# LightingUPS_v2b.net
KiCad netlist of a schematic drawn in EAGLE
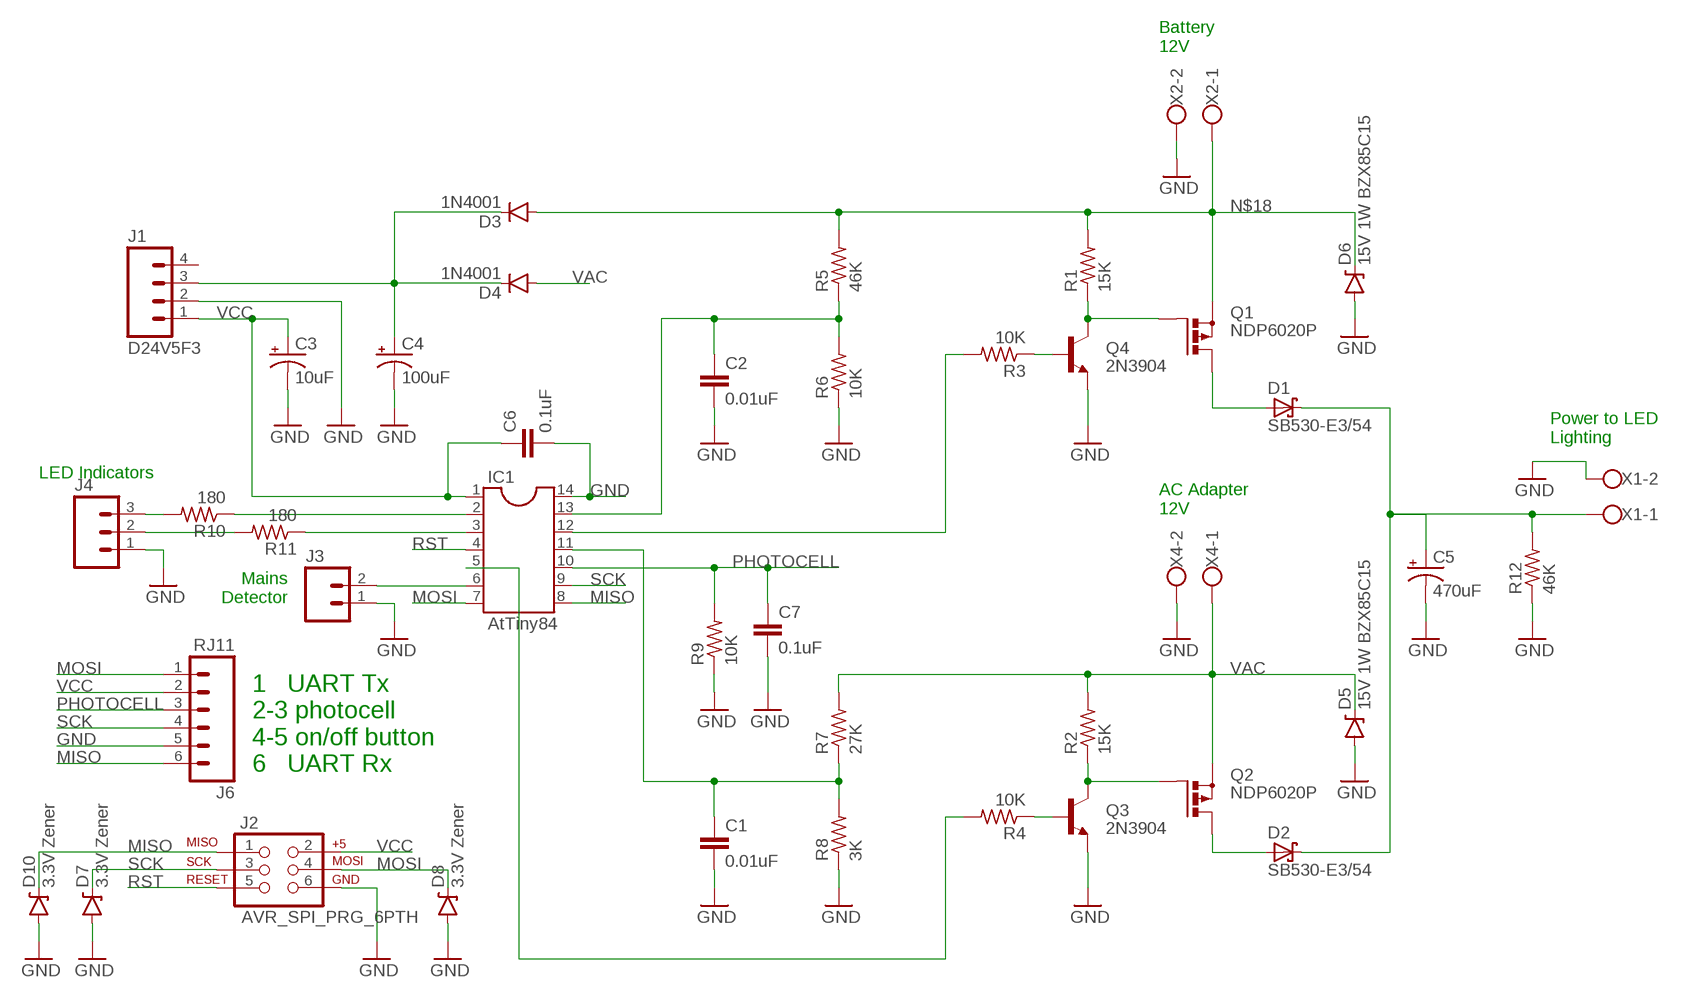
[diagram p0: schematic, sheet 1]

(export (version "E")
  (design (tool "Eeschema 10.0.6"))
  (components
    (comp (ref "C1")
      (value "0.01uF")
      (footprint "eagle-import:CAP-PTH-5MM")
      (libsource (lib "eagle-import") (part "SparkFun-Passives_CAPPTH1"))
    )
    (comp (ref "C2")
      (value "0.01uF")
      (footprint "eagle-import:CAP-PTH-5MM")
      (libsource (lib "eagle-import") (part "SparkFun-Passives_CAPPTH1"))
    )
    (comp (ref "C3")
      (value "10uF")
      (footprint "eagle-import:CPOL-RADIAL-100UF-25V")
      (libsource (lib "eagle-import") (part "CAP_POLPTH1"))
    )
    (comp (ref "C4")
      (value "100uF")
      (footprint "eagle-import:CPOL-RADIAL-100UF-25V")
      (libsource (lib "eagle-import") (part "CAP_POLPTH1"))
    )
    (comp (ref "C5")
      (value "470uF")
      (footprint "eagle-import:CPOL-RADIAL-1000UF-25V")
      (libsource (lib "eagle-import") (part "CAP_POLPTH4"))
    )
    (comp (ref "C6")
      (value "0.1uF")
      (footprint "eagle-import:CAP-PTH-SMALL")
      (libsource (lib "eagle-import") (part "CAPPTH"))
    )
    (comp (ref "C7")
      (value "0.1uF")
      (footprint "eagle-import:CAP-PTH-SMALL")
      (libsource (lib "eagle-import") (part "CAPPTH"))
    )
    (comp (ref "D1")
      (value "SB530-E3/54")
      (footprint "eagle-import:DO201T15")
      (libsource (lib "eagle-import") (part "SCHOTTKY-DIODEDO201T15"))
    )
    (comp (ref "D2")
      (value "SB530-E3/54")
      (footprint "eagle-import:DO201T15")
      (libsource (lib "eagle-import") (part "SCHOTTKY-DIODEDO201T15"))
    )
    (comp (ref "D3")
      (value "1N4001")
      (footprint "eagle-import:DIODE-1N4001")
      (libsource (lib "eagle-import") (part "DIODEPTH"))
    )
    (comp (ref "D4")
      (value "1N4001")
      (footprint "eagle-import:DIODE-1N4001")
      (libsource (lib "eagle-import") (part "DIODEPTH"))
    )
    (comp (ref "D5")
      (value "15V 1W BZX85C15")
      (footprint "eagle-import:DIODE-ZENER")
      (libsource (lib "eagle-import") (part "DIODE-ZENERPTH"))
    )
    (comp (ref "D6")
      (value "15V 1W BZX85C15")
      (footprint "eagle-import:DIODE-ZENER")
      (libsource (lib "eagle-import") (part "DIODE-ZENERPTH"))
    )
    (comp (ref "D7")
      (value "3.3V Zener")
      (footprint "eagle-import:DIODE-ZENER")
      (libsource (lib "eagle-import") (part "DIODE-ZENERPTH"))
    )
    (comp (ref "D8")
      (value "3.3V Zener")
      (footprint "eagle-import:DIODE-ZENER")
      (libsource (lib "eagle-import") (part "DIODE-ZENERPTH"))
    )
    (comp (ref "D10")
      (value "3.3V Zener")
      (footprint "eagle-import:DIODE-ZENER")
      (libsource (lib "eagle-import") (part "DIODE-ZENERPTH"))
    )
    (comp (ref "IC1")
      (value "AtTiny84")
      (footprint "eagle-import:DIL14")
      (libsource (lib "eagle-import") (part "DIL14"))
    )
    (comp (ref "J1")
      (value "D24V5F3")
      (footprint "eagle-import:1X04")
      (libsource (lib "eagle-import") (part "M04PTH"))
    )
    (comp (ref "J2")
      (value "AVR_SPI_PRG_6PTH")
      (footprint "eagle-import:2X3")
      (libsource (lib "eagle-import") (part "AVR_SPI_PRG_6PTH"))
    )
    (comp (ref "J3")
      (value "M02PTH")
      (footprint "eagle-import:1X02")
      (libsource (lib "eagle-import") (part "M02PTH"))
    )
    (comp (ref "J4")
      (value "M03PTH")
      (footprint "eagle-import:1X03")
      (libsource (lib "eagle-import") (part "M03PTH"))
    )
    (comp (ref "J6")
      (value "RJ11")
      (footprint "eagle-import:RJ11-6")
      (libsource (lib "eagle-import") (part "RJ11-6PTH"))
    )
    (comp (ref "Q1")
      (value "NDP6020P")
      (footprint "eagle-import:TO220BV")
      (libsource (lib "eagle-import") (part "PMOSFET_PTO220BV"))
    )
    (comp (ref "Q2")
      (value "NDP6020P")
      (footprint "eagle-import:TO220BV")
      (libsource (lib "eagle-import") (part "PMOSFET_PTO220BV"))
    )
    (comp (ref "Q3")
      (value "2N3904")
      (footprint "eagle-import:TO-92-AMMO")
      (libsource (lib "eagle-import") (part "TRANSISTOR_NPNTO-92-AMMO"))
    )
    (comp (ref "Q4")
      (value "2N3904")
      (footprint "eagle-import:TO-92-AMMO")
      (libsource (lib "eagle-import") (part "TRANSISTOR_NPNTO-92-AMMO"))
    )
    (comp (ref "R1")
      (value "15K")
      (footprint "eagle-import:0204_5")
      (libsource (lib "eagle-import") (part "R-US_0204/5"))
    )
    (comp (ref "R2")
      (value "15K")
      (footprint "eagle-import:0204_5")
      (libsource (lib "eagle-import") (part "R-US_0204/5"))
    )
    (comp (ref "R3")
      (value "10K")
      (footprint "eagle-import:0204_5")
      (libsource (lib "eagle-import") (part "R-US_0204/5"))
    )
    (comp (ref "R4")
      (value "10K")
      (footprint "eagle-import:0204_5")
      (libsource (lib "eagle-import") (part "R-US_0204/5"))
    )
    (comp (ref "R5")
      (value "46K")
      (footprint "eagle-import:0204_5")
      (libsource (lib "eagle-import") (part "R-US_0204/5"))
    )
    (comp (ref "R6")
      (value "10K")
      (footprint "eagle-import:0204_5")
      (libsource (lib "eagle-import") (part "R-US_0204/5"))
    )
    (comp (ref "R7")
      (value "27K")
      (footprint "eagle-import:0204_5")
      (libsource (lib "eagle-import") (part "R-US_0204/5"))
    )
    (comp (ref "R8")
      (value "3K")
      (footprint "eagle-import:0204_5")
      (libsource (lib "eagle-import") (part "R-US_0204/5"))
    )
    (comp (ref "R9")
      (value "10K")
      (footprint "eagle-import:0204_5")
      (libsource (lib "eagle-import") (part "R-US_0204/5"))
    )
    (comp (ref "R10")
      (value "180")
      (footprint "eagle-import:0204_5")
      (libsource (lib "eagle-import") (part "R-US_0204/5"))
    )
    (comp (ref "R11")
      (value "180")
      (footprint "eagle-import:0204_5")
      (libsource (lib "eagle-import") (part "R-US_0204/5"))
    )
    (comp (ref "R12")
      (value "46K")
      (footprint "eagle-import:0204_5")
      (libsource (lib "eagle-import") (part "R-US_0204/5"))
    )
    (comp (ref "X1")
      (value "W237-102")
      (footprint "eagle-import:W237-102")
      (fields (field (name "MPN") "237-102"))
      (libsource (lib "eagle-import") (part "W237-102"))
    )
    (comp (ref "X2")
      (value "W237-102")
      (footprint "eagle-import:W237-102")
      (fields (field (name "MPN") "237-102"))
      (libsource (lib "eagle-import") (part "W237-102"))
    )
    (comp (ref "X4")
      (value "W237-102")
      (footprint "eagle-import:W237-102")
      (fields (field (name "MPN") "237-102"))
      (libsource (lib "eagle-import") (part "W237-102"))
    )
  )
  (nets
    (net (code "1") (name "/MISO") (class "Default")
      (node (ref "D10") (pin "P$1") (pinfunction "C_P$1") (pintype "passive"))
      (node (ref "IC1") (pin "8") (pinfunction "8_8") (pintype "passive"))
      (node (ref "J2") (pin "1") (pinfunction "1_1") (pintype "passive"))
      (node (ref "J6") (pin "6") (pinfunction "6_6") (pintype "passive"))
    )
    (net (code "2") (name "/MOSI") (class "Default")
      (node (ref "D8") (pin "P$1") (pinfunction "C_P$1") (pintype "passive"))
      (node (ref "IC1") (pin "7") (pinfunction "7_7") (pintype "passive"))
      (node (ref "J2") (pin "4") (pinfunction "4_4") (pintype "passive"))
      (node (ref "J6") (pin "1") (pinfunction "1_1") (pintype "passive"))
    )
    (net (code "3") (name "/N$18") (class "Default")
      (node (ref "D3") (pin "A") (pinfunction "A_A") (pintype "passive"))
      (node (ref "D6") (pin "P$1") (pinfunction "C_P$1") (pintype "passive"))
      (node (ref "Q1") (pin "S") (pinfunction "S_S") (pintype "passive"))
      (node (ref "R1") (pin "2") (pinfunction "2_2") (pintype "passive"))
      (node (ref "R5") (pin "2") (pinfunction "2_2") (pintype "passive"))
      (node (ref "X2") (pin "1") (pinfunction "KL_1") (pintype "passive"))
    )
    (net (code "4") (name "/PHOTOCELL") (class "Default")
      (node (ref "C7") (pin "1") (pinfunction "1_1") (pintype "passive"))
      (node (ref "IC1") (pin "10") (pinfunction "10_10") (pintype "passive"))
      (node (ref "J6") (pin "3") (pinfunction "3_3") (pintype "passive"))
      (node (ref "R9") (pin "2") (pinfunction "2_2") (pintype "passive"))
    )
    (net (code "5") (name "/RST") (class "Default")
      (node (ref "IC1") (pin "4") (pinfunction "4_4") (pintype "passive"))
      (node (ref "J2") (pin "5") (pinfunction "5_5") (pintype "passive"))
    )
    (net (code "6") (name "/SCK") (class "Default")
      (node (ref "D7") (pin "P$1") (pinfunction "C_P$1") (pintype "passive"))
      (node (ref "IC1") (pin "9") (pinfunction "9_9") (pintype "passive"))
      (node (ref "J2") (pin "3") (pinfunction "3_3") (pintype "passive"))
      (node (ref "J6") (pin "4") (pinfunction "4_4") (pintype "passive"))
    )
    (net (code "7") (name "/VAC") (class "Default")
      (node (ref "D4") (pin "A") (pinfunction "A_A") (pintype "passive"))
      (node (ref "D5") (pin "P$1") (pinfunction "C_P$1") (pintype "passive"))
      (node (ref "Q2") (pin "S") (pinfunction "S_S") (pintype "passive"))
      (node (ref "R2") (pin "2") (pinfunction "2_2") (pintype "passive"))
      (node (ref "R7") (pin "2") (pinfunction "2_2") (pintype "passive"))
      (node (ref "X4") (pin "1") (pinfunction "KL_1") (pintype "passive"))
    )
    (net (code "8") (name "/VCC") (class "Default")
      (node (ref "C3") (pin "1") (pinfunction "+_1") (pintype "passive"))
      (node (ref "C6") (pin "1") (pinfunction "1_1") (pintype "passive"))
      (node (ref "IC1") (pin "1") (pinfunction "1_1") (pintype "passive"))
      (node (ref "J1") (pin "1") (pinfunction "1_1") (pintype "passive"))
      (node (ref "J2") (pin "2") (pinfunction "2_2") (pintype "passive"))
      (node (ref "J6") (pin "2") (pinfunction "2_2") (pintype "passive"))
    )
    (net (code "9") (name "GND") (class "Default")
      (node (ref "C1") (pin "2") (pinfunction "2_2") (pintype "passive"))
      (node (ref "C2") (pin "2") (pinfunction "2_2") (pintype "passive"))
      (node (ref "C3") (pin "2") (pinfunction "-_2") (pintype "passive"))
      (node (ref "C4") (pin "2") (pinfunction "-_2") (pintype "passive"))
      (node (ref "C5") (pin "-") (pinfunction "-_-") (pintype "passive"))
      (node (ref "C6") (pin "2") (pinfunction "2_2") (pintype "passive"))
      (node (ref "C7") (pin "2") (pinfunction "2_2") (pintype "passive"))
      (node (ref "D10") (pin "P$2") (pinfunction "A_P$2") (pintype "passive"))
      (node (ref "D5") (pin "P$2") (pinfunction "A_P$2") (pintype "passive"))
      (node (ref "D6") (pin "P$2") (pinfunction "A_P$2") (pintype "passive"))
      (node (ref "D7") (pin "P$2") (pinfunction "A_P$2") (pintype "passive"))
      (node (ref "D8") (pin "P$2") (pinfunction "A_P$2") (pintype "passive"))
      (node (ref "IC1") (pin "14") (pinfunction "14_14") (pintype "passive"))
      (node (ref "J1") (pin "2") (pinfunction "2_2") (pintype "passive"))
      (node (ref "J2") (pin "6") (pinfunction "6_6") (pintype "passive"))
      (node (ref "J3") (pin "1") (pinfunction "1_1") (pintype "passive"))
      (node (ref "J4") (pin "1") (pinfunction "1_1") (pintype "passive"))
      (node (ref "J6") (pin "5") (pinfunction "5_5") (pintype "passive"))
      (node (ref "Q3") (pin "1") (pinfunction "E_1") (pintype "passive"))
      (node (ref "Q4") (pin "1") (pinfunction "E_1") (pintype "passive"))
      (node (ref "R12") (pin "1") (pinfunction "1_1") (pintype "passive"))
      (node (ref "R6") (pin "1") (pinfunction "1_1") (pintype "passive"))
      (node (ref "R8") (pin "1") (pinfunction "1_1") (pintype "passive"))
      (node (ref "R9") (pin "1") (pinfunction "1_1") (pintype "passive"))
      (node (ref "X1") (pin "2") (pinfunction "KL_2") (pintype "passive"))
      (node (ref "X2") (pin "2") (pinfunction "KL_2") (pintype "passive"))
      (node (ref "X4") (pin "2") (pinfunction "KL_2") (pintype "passive"))
    )
    (net (code "10") (name "Net-(C1-Pad1)") (class "Default")
      (node (ref "C1") (pin "1") (pinfunction "1_1") (pintype "passive"))
      (node (ref "IC1") (pin "11") (pinfunction "11_11") (pintype "passive"))
      (node (ref "R7") (pin "1") (pinfunction "1_1") (pintype "passive"))
      (node (ref "R8") (pin "2") (pinfunction "2_2") (pintype "passive"))
    )
    (net (code "11") (name "Net-(C2-Pad1)") (class "Default")
      (node (ref "C2") (pin "1") (pinfunction "1_1") (pintype "passive"))
      (node (ref "IC1") (pin "13") (pinfunction "13_13") (pintype "passive"))
      (node (ref "R5") (pin "1") (pinfunction "1_1") (pintype "passive"))
      (node (ref "R6") (pin "2") (pinfunction "2_2") (pintype "passive"))
    )
    (net (code "12") (name "Net-(C4-+)") (class "Default")
      (node (ref "C4") (pin "1") (pinfunction "+_1") (pintype "passive"))
      (node (ref "D3") (pin "C") (pinfunction "C_C") (pintype "passive"))
      (node (ref "D4") (pin "C") (pinfunction "C_C") (pintype "passive"))
      (node (ref "J1") (pin "3") (pinfunction "3_3") (pintype "passive"))
    )
    (net (code "13") (name "Net-(D1-PadA)") (class "Default")
      (node (ref "D1") (pin "A") (pinfunction "A_A") (pintype "passive"))
      (node (ref "Q1") (pin "D") (pinfunction "D_D") (pintype "passive"))
    )
    (net (code "14") (name "Net-(D2-PadA)") (class "Default")
      (node (ref "D2") (pin "A") (pinfunction "A_A") (pintype "passive"))
      (node (ref "Q2") (pin "D") (pinfunction "D_D") (pintype "passive"))
    )
    (net (code "15") (name "Net-(IC1-Pad2)") (class "Default")
      (node (ref "IC1") (pin "2") (pinfunction "2_2") (pintype "passive"))
      (node (ref "R10") (pin "1") (pinfunction "1_1") (pintype "passive"))
    )
    (net (code "16") (name "Net-(IC1-Pad3)") (class "Default")
      (node (ref "IC1") (pin "3") (pinfunction "3_3") (pintype "passive"))
      (node (ref "R11") (pin "1") (pinfunction "1_1") (pintype "passive"))
    )
    (net (code "17") (name "Net-(IC1-Pad5)") (class "Default")
      (node (ref "IC1") (pin "5") (pinfunction "5_5") (pintype "passive"))
      (node (ref "R4") (pin "2") (pinfunction "2_2") (pintype "passive"))
    )
    (net (code "18") (name "Net-(IC1-Pad6)") (class "Default")
      (node (ref "IC1") (pin "6") (pinfunction "6_6") (pintype "passive"))
      (node (ref "J3") (pin "2") (pinfunction "2_2") (pintype "passive"))
    )
    (net (code "19") (name "Net-(IC1-Pad12)") (class "Default")
      (node (ref "IC1") (pin "12") (pinfunction "12_12") (pintype "passive"))
      (node (ref "R3") (pin "2") (pinfunction "2_2") (pintype "passive"))
    )
    (net (code "20") (name "Net-(J4-Pad2)") (class "Default")
      (node (ref "J4") (pin "2") (pinfunction "2_2") (pintype "passive"))
      (node (ref "R11") (pin "2") (pinfunction "2_2") (pintype "passive"))
    )
    (net (code "21") (name "Net-(J4-Pad3)") (class "Default")
      (node (ref "J4") (pin "3") (pinfunction "3_3") (pintype "passive"))
      (node (ref "R10") (pin "2") (pinfunction "2_2") (pintype "passive"))
    )
    (net (code "22") (name "Net-(Q3-B)") (class "Default")
      (node (ref "Q3") (pin "2") (pinfunction "B_2") (pintype "passive"))
      (node (ref "R4") (pin "1") (pinfunction "1_1") (pintype "passive"))
    )
    (net (code "23") (name "Net-(Q3-C)") (class "Default")
      (node (ref "Q2") (pin "G") (pinfunction "G_G") (pintype "passive"))
      (node (ref "Q3") (pin "3") (pinfunction "C_3") (pintype "passive"))
      (node (ref "R2") (pin "1") (pinfunction "1_1") (pintype "passive"))
    )
    (net (code "24") (name "Net-(Q4-B)") (class "Default")
      (node (ref "Q4") (pin "2") (pinfunction "B_2") (pintype "passive"))
      (node (ref "R3") (pin "1") (pinfunction "1_1") (pintype "passive"))
    )
    (net (code "25") (name "Net-(Q4-C)") (class "Default")
      (node (ref "Q1") (pin "G") (pinfunction "G_G") (pintype "passive"))
      (node (ref "Q4") (pin "3") (pinfunction "C_3") (pintype "passive"))
      (node (ref "R1") (pin "1") (pinfunction "1_1") (pintype "passive"))
    )
    (net (code "26") (name "Net-(X1A-KL)") (class "Default")
      (node (ref "C5") (pin "+") (pinfunction "+_+") (pintype "passive"))
      (node (ref "D1") (pin "C") (pinfunction "C_C") (pintype "passive"))
      (node (ref "D2") (pin "C") (pinfunction "C_C") (pintype "passive"))
      (node (ref "R12") (pin "2") (pinfunction "2_2") (pintype "passive"))
      (node (ref "X1") (pin "1") (pinfunction "KL_1") (pintype "passive"))
    )
    (net (code "27") (name "unconnected-(J1-Pad4)") (class "Default")
      (node (ref "J1") (pin "4") (pinfunction "4_4") (pintype "passive"))
    )
  )
)
